# Sheet1.net
KiCad netlist of a schematic drawn in Altium Designer
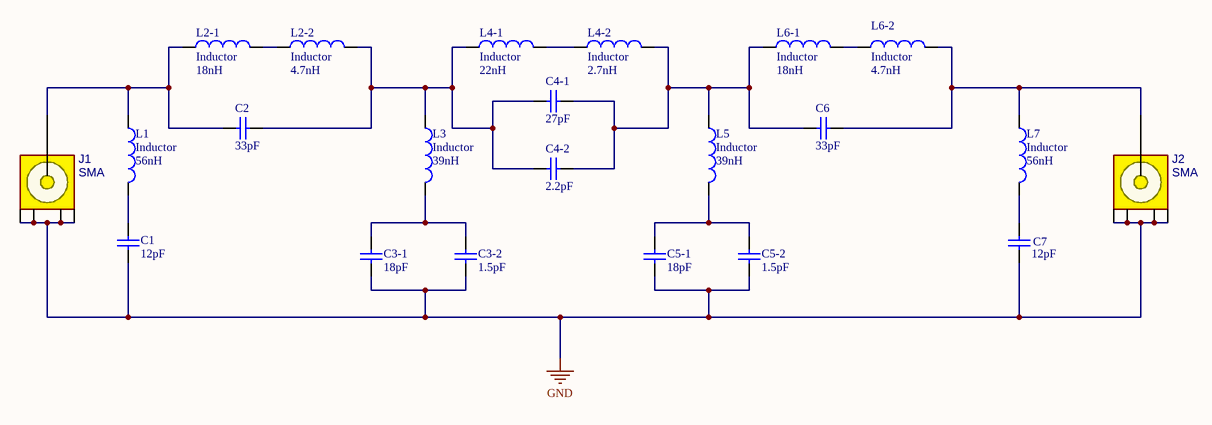
[diagram p0: Sheet1.SchDoc]

(export (version "E")
  (design (tool "Eeschema 10.0.6"))
  (components
    (comp (ref "C1")
      (value "12pF")
      (footprint "CAP0805")
      (description "TOTAL CAPACITOR SMD PACK")
      (fields (field (name "DESIGNER") "Abbas Basereh"))
      (libsource (lib "Altium") (part "CAP SMD PACKAGE"))
    )
    (comp (ref "C2")
      (value "33pF")
      (footprint "CAP0805")
      (description "TOTAL CAPACITOR SMD PACK")
      (fields (field (name "DESIGNER") "Abbas Basereh"))
      (libsource (lib "Altium") (part "CAP SMD PACKAGE"))
    )
    (comp (ref "C3-1")
      (value "18pF")
      (footprint "CAP0805")
      (description "TOTAL CAPACITOR SMD PACK")
      (fields (field (name "DESIGNER") "Abbas Basereh"))
      (libsource (lib "Altium") (part "CAP SMD PACKAGE"))
    )
    (comp (ref "C3-2")
      (value "1.5pF")
      (footprint "CAP0805")
      (description "TOTAL CAPACITOR SMD PACK")
      (fields (field (name "DESIGNER") "Abbas Basereh"))
      (libsource (lib "Altium") (part "CAP SMD PACKAGE"))
    )
    (comp (ref "C4-1")
      (value "27pF")
      (footprint "CAP0805")
      (description "TOTAL CAPACITOR SMD PACK")
      (fields (field (name "DESIGNER") "Abbas Basereh"))
      (libsource (lib "Altium") (part "CAP SMD PACKAGE"))
    )
    (comp (ref "C4-2")
      (value "2.2pF")
      (footprint "CAP0805")
      (description "TOTAL CAPACITOR SMD PACK")
      (fields (field (name "DESIGNER") "Abbas Basereh"))
      (libsource (lib "Altium") (part "CAP SMD PACKAGE"))
    )
    (comp (ref "C5-1")
      (value "18pF")
      (footprint "CAP0805")
      (description "TOTAL CAPACITOR SMD PACK")
      (fields (field (name "DESIGNER") "Abbas Basereh"))
      (libsource (lib "Altium") (part "CAP SMD PACKAGE"))
    )
    (comp (ref "C5-2")
      (value "1.5pF")
      (footprint "CAP0805")
      (description "TOTAL CAPACITOR SMD PACK")
      (fields (field (name "DESIGNER") "Abbas Basereh"))
      (libsource (lib "Altium") (part "CAP SMD PACKAGE"))
    )
    (comp (ref "C6")
      (value "33pF")
      (footprint "CAP0805")
      (description "TOTAL CAPACITOR SMD PACK")
      (fields (field (name "DESIGNER") "Abbas Basereh"))
      (libsource (lib "Altium") (part "CAP SMD PACKAGE"))
    )
    (comp (ref "C7")
      (value "12pF")
      (footprint "CAP0805")
      (description "TOTAL CAPACITOR SMD PACK")
      (fields (field (name "DESIGNER") "Abbas Basereh"))
      (libsource (lib "Altium") (part "CAP SMD PACKAGE"))
    )
    (comp (ref "J1")
      (value "SMA")
      (footprint "SMA_EM")
      (description "CONN, RF, SMA, Edge mounting")
      (fields (field (name "MANF_P#") "SMA-J-P-H-ST-EM1") (field (name "MANF") "Samtec"))
      (libsource (lib "conn_rf") (part "CONN_RF_SMA_EM"))
    )
    (comp (ref "J2")
      (value "SMA")
      (footprint "SMA_EM")
      (description "CONN, RF, SMA, Edge mounting")
      (fields (field (name "MANF_P#") "SMA-J-P-H-ST-EM1") (field (name "MANF") "Samtec"))
      (libsource (lib "conn_rf") (part "CONN_RF_SMA_EM"))
    )
    (comp (ref "L1")
      (value "Inductor")
      (footprint "0402-A")
      (fields (field (name "ALTIUM_VALUE") "56nH") (field (name "PUBLISHER") "Altium Limited"))
      (libsource (lib "Miscellaneous Devices") (part "Inductor"))
    )
    (comp (ref "L2-1")
      (value "Inductor")
      (footprint "INDC1608L")
      (fields (field (name "ALTIUM_VALUE") "18nH") (field (name "PUBLISHER") "Altium Limited"))
      (libsource (lib "Altium") (part "Inductor"))
    )
    (comp (ref "L2-2")
      (value "Inductor")
      (footprint "INDC1608L")
      (fields (field (name "ALTIUM_VALUE") "4.7nH") (field (name "PUBLISHER") "Altium Limited"))
      (libsource (lib "Altium") (part "Inductor"))
    )
    (comp (ref "L3")
      (value "Inductor")
      (footprint "0402-A")
      (fields (field (name "ALTIUM_VALUE") "39nH") (field (name "PUBLISHER") "Altium Limited"))
      (libsource (lib "Miscellaneous Devices") (part "Inductor"))
    )
    (comp (ref "L4-1")
      (value "Inductor")
      (footprint "0402-A")
      (fields (field (name "ALTIUM_VALUE") "22nH") (field (name "PUBLISHER") "Altium Limited"))
      (libsource (lib "Miscellaneous Devices") (part "Inductor"))
    )
    (comp (ref "L4-2")
      (value "Inductor")
      (footprint "0402-A")
      (fields (field (name "ALTIUM_VALUE") "2.7nH") (field (name "PUBLISHER") "Altium Limited"))
      (libsource (lib "Miscellaneous Devices") (part "Inductor"))
    )
    (comp (ref "L5")
      (value "Inductor")
      (footprint "0402-A")
      (fields (field (name "ALTIUM_VALUE") "39nH") (field (name "PUBLISHER") "Altium Limited"))
      (libsource (lib "Miscellaneous Devices") (part "Inductor"))
    )
    (comp (ref "L6-1")
      (value "Inductor")
      (footprint "0402-A")
      (fields (field (name "ALTIUM_VALUE") "18nH") (field (name "PUBLISHER") "Altium Limited"))
      (libsource (lib "Miscellaneous Devices") (part "Inductor"))
    )
    (comp (ref "L6-2")
      (value "Inductor")
      (footprint "0402-A")
      (fields (field (name "ALTIUM_VALUE") "4.7nH") (field (name "PUBLISHER") "Altium Limited"))
      (libsource (lib "Miscellaneous Devices") (part "Inductor"))
    )
    (comp (ref "L7")
      (value "Inductor")
      (footprint "0402-A")
      (fields (field (name "ALTIUM_VALUE") "56nH") (field (name "PUBLISHER") "Altium Limited"))
      (libsource (lib "Miscellaneous Devices") (part "Inductor"))
    )
  )
  (nets
    (net (code "1") (name "GND") (class "Default")
      (node (ref "C1") (pin "1") (pinfunction "1_1") (pintype "passive"))
      (node (ref "C3-1") (pin "1") (pinfunction "1_1") (pintype "passive"))
      (node (ref "C3-2") (pin "1") (pinfunction "1_1") (pintype "passive"))
      (node (ref "C5-1") (pin "1") (pinfunction "1_1") (pintype "passive"))
      (node (ref "C5-2") (pin "1") (pinfunction "1_1") (pintype "passive"))
      (node (ref "C7") (pin "1") (pinfunction "1_1") (pintype "passive"))
      (node (ref "J1") (pin "2") (pinfunction "G1_2") (pintype "passive"))
      (node (ref "J1") (pin "3") (pinfunction "G2_3") (pintype "passive"))
      (node (ref "J1") (pin "4") (pinfunction "G3_4") (pintype "passive"))
      (node (ref "J1") (pin "5") (pinfunction "G4_5") (pintype "passive"))
      (node (ref "J2") (pin "2") (pinfunction "G1_2") (pintype "passive"))
      (node (ref "J2") (pin "3") (pinfunction "G2_3") (pintype "passive"))
      (node (ref "J2") (pin "4") (pinfunction "G3_4") (pintype "passive"))
      (node (ref "J2") (pin "5") (pinfunction "G4_5") (pintype "passive"))
    )
    (net (code "2") (name "Net-(C1-Pad2)") (class "Default")
      (node (ref "C1") (pin "2") (pinfunction "2_2") (pintype "passive"))
      (node (ref "L1") (pin "2") (pinfunction "2_2") (pintype "passive"))
    )
    (net (code "3") (name "Net-(C2-Pad1)") (class "Default")
      (node (ref "C2") (pin "1") (pinfunction "1_1") (pintype "passive"))
      (node (ref "C4-1") (pin "2") (pinfunction "2_2") (pintype "passive"))
      (node (ref "C4-2") (pin "2") (pinfunction "2_2") (pintype "passive"))
      (node (ref "L2-2") (pin "2") (pinfunction "2_2") (pintype "passive"))
      (node (ref "L3") (pin "1") (pinfunction "1_1") (pintype "passive"))
      (node (ref "L4-1") (pin "1") (pinfunction "1_1") (pintype "passive"))
    )
    (net (code "4") (name "Net-(C3-1-Pad2)") (class "Default")
      (node (ref "C3-1") (pin "2") (pinfunction "2_2") (pintype "passive"))
      (node (ref "C3-2") (pin "2") (pinfunction "2_2") (pintype "passive"))
      (node (ref "L3") (pin "2") (pinfunction "2_2") (pintype "passive"))
    )
    (net (code "5") (name "Net-(C4-1-Pad1)") (class "Default")
      (node (ref "C4-1") (pin "1") (pinfunction "1_1") (pintype "passive"))
      (node (ref "C4-2") (pin "1") (pinfunction "1_1") (pintype "passive"))
      (node (ref "C6") (pin "2") (pinfunction "2_2") (pintype "passive"))
      (node (ref "L4-2") (pin "2") (pinfunction "2_2") (pintype "passive"))
      (node (ref "L5") (pin "1") (pinfunction "1_1") (pintype "passive"))
      (node (ref "L6-1") (pin "1") (pinfunction "1_1") (pintype "passive"))
    )
    (net (code "6") (name "Net-(C5-1-Pad2)") (class "Default")
      (node (ref "C5-1") (pin "2") (pinfunction "2_2") (pintype "passive"))
      (node (ref "C5-2") (pin "2") (pinfunction "2_2") (pintype "passive"))
      (node (ref "L5") (pin "2") (pinfunction "2_2") (pintype "passive"))
    )
    (net (code "7") (name "Net-(C7-Pad2)") (class "Default")
      (node (ref "C7") (pin "2") (pinfunction "2_2") (pintype "passive"))
      (node (ref "L7") (pin "2") (pinfunction "2_2") (pintype "passive"))
    )
    (net (code "8") (name "Net-(J1-SIG)") (class "Default")
      (node (ref "C2") (pin "2") (pinfunction "2_2") (pintype "passive"))
      (node (ref "J1") (pin "1") (pinfunction "SIG_1") (pintype "passive"))
      (node (ref "L1") (pin "1") (pinfunction "1_1") (pintype "passive"))
      (node (ref "L2-1") (pin "1") (pinfunction "1_1") (pintype "passive"))
    )
    (net (code "9") (name "Net-(J2-SIG)") (class "Default")
      (node (ref "C6") (pin "1") (pinfunction "1_1") (pintype "passive"))
      (node (ref "J2") (pin "1") (pinfunction "SIG_1") (pintype "passive"))
      (node (ref "L6-2") (pin "2") (pinfunction "2_2") (pintype "passive"))
      (node (ref "L7") (pin "1") (pinfunction "1_1") (pintype "passive"))
    )
    (net (code "10") (name "Net-(L2-1-Pad2)") (class "Default")
      (node (ref "L2-1") (pin "2") (pinfunction "2_2") (pintype "passive"))
      (node (ref "L2-2") (pin "1") (pinfunction "1_1") (pintype "passive"))
    )
    (net (code "11") (name "Net-(L4-1-Pad2)") (class "Default")
      (node (ref "L4-1") (pin "2") (pinfunction "2_2") (pintype "passive"))
      (node (ref "L4-2") (pin "1") (pinfunction "1_1") (pintype "passive"))
    )
    (net (code "12") (name "Net-(L6-1-Pad2)") (class "Default")
      (node (ref "L6-1") (pin "2") (pinfunction "2_2") (pintype "passive"))
      (node (ref "L6-2") (pin "1") (pinfunction "1_1") (pintype "passive"))
    )
  )
)
